# MCU-DESKTOP-L9L0IAD.net
KiCad netlist of a schematic drawn in Altium Designer
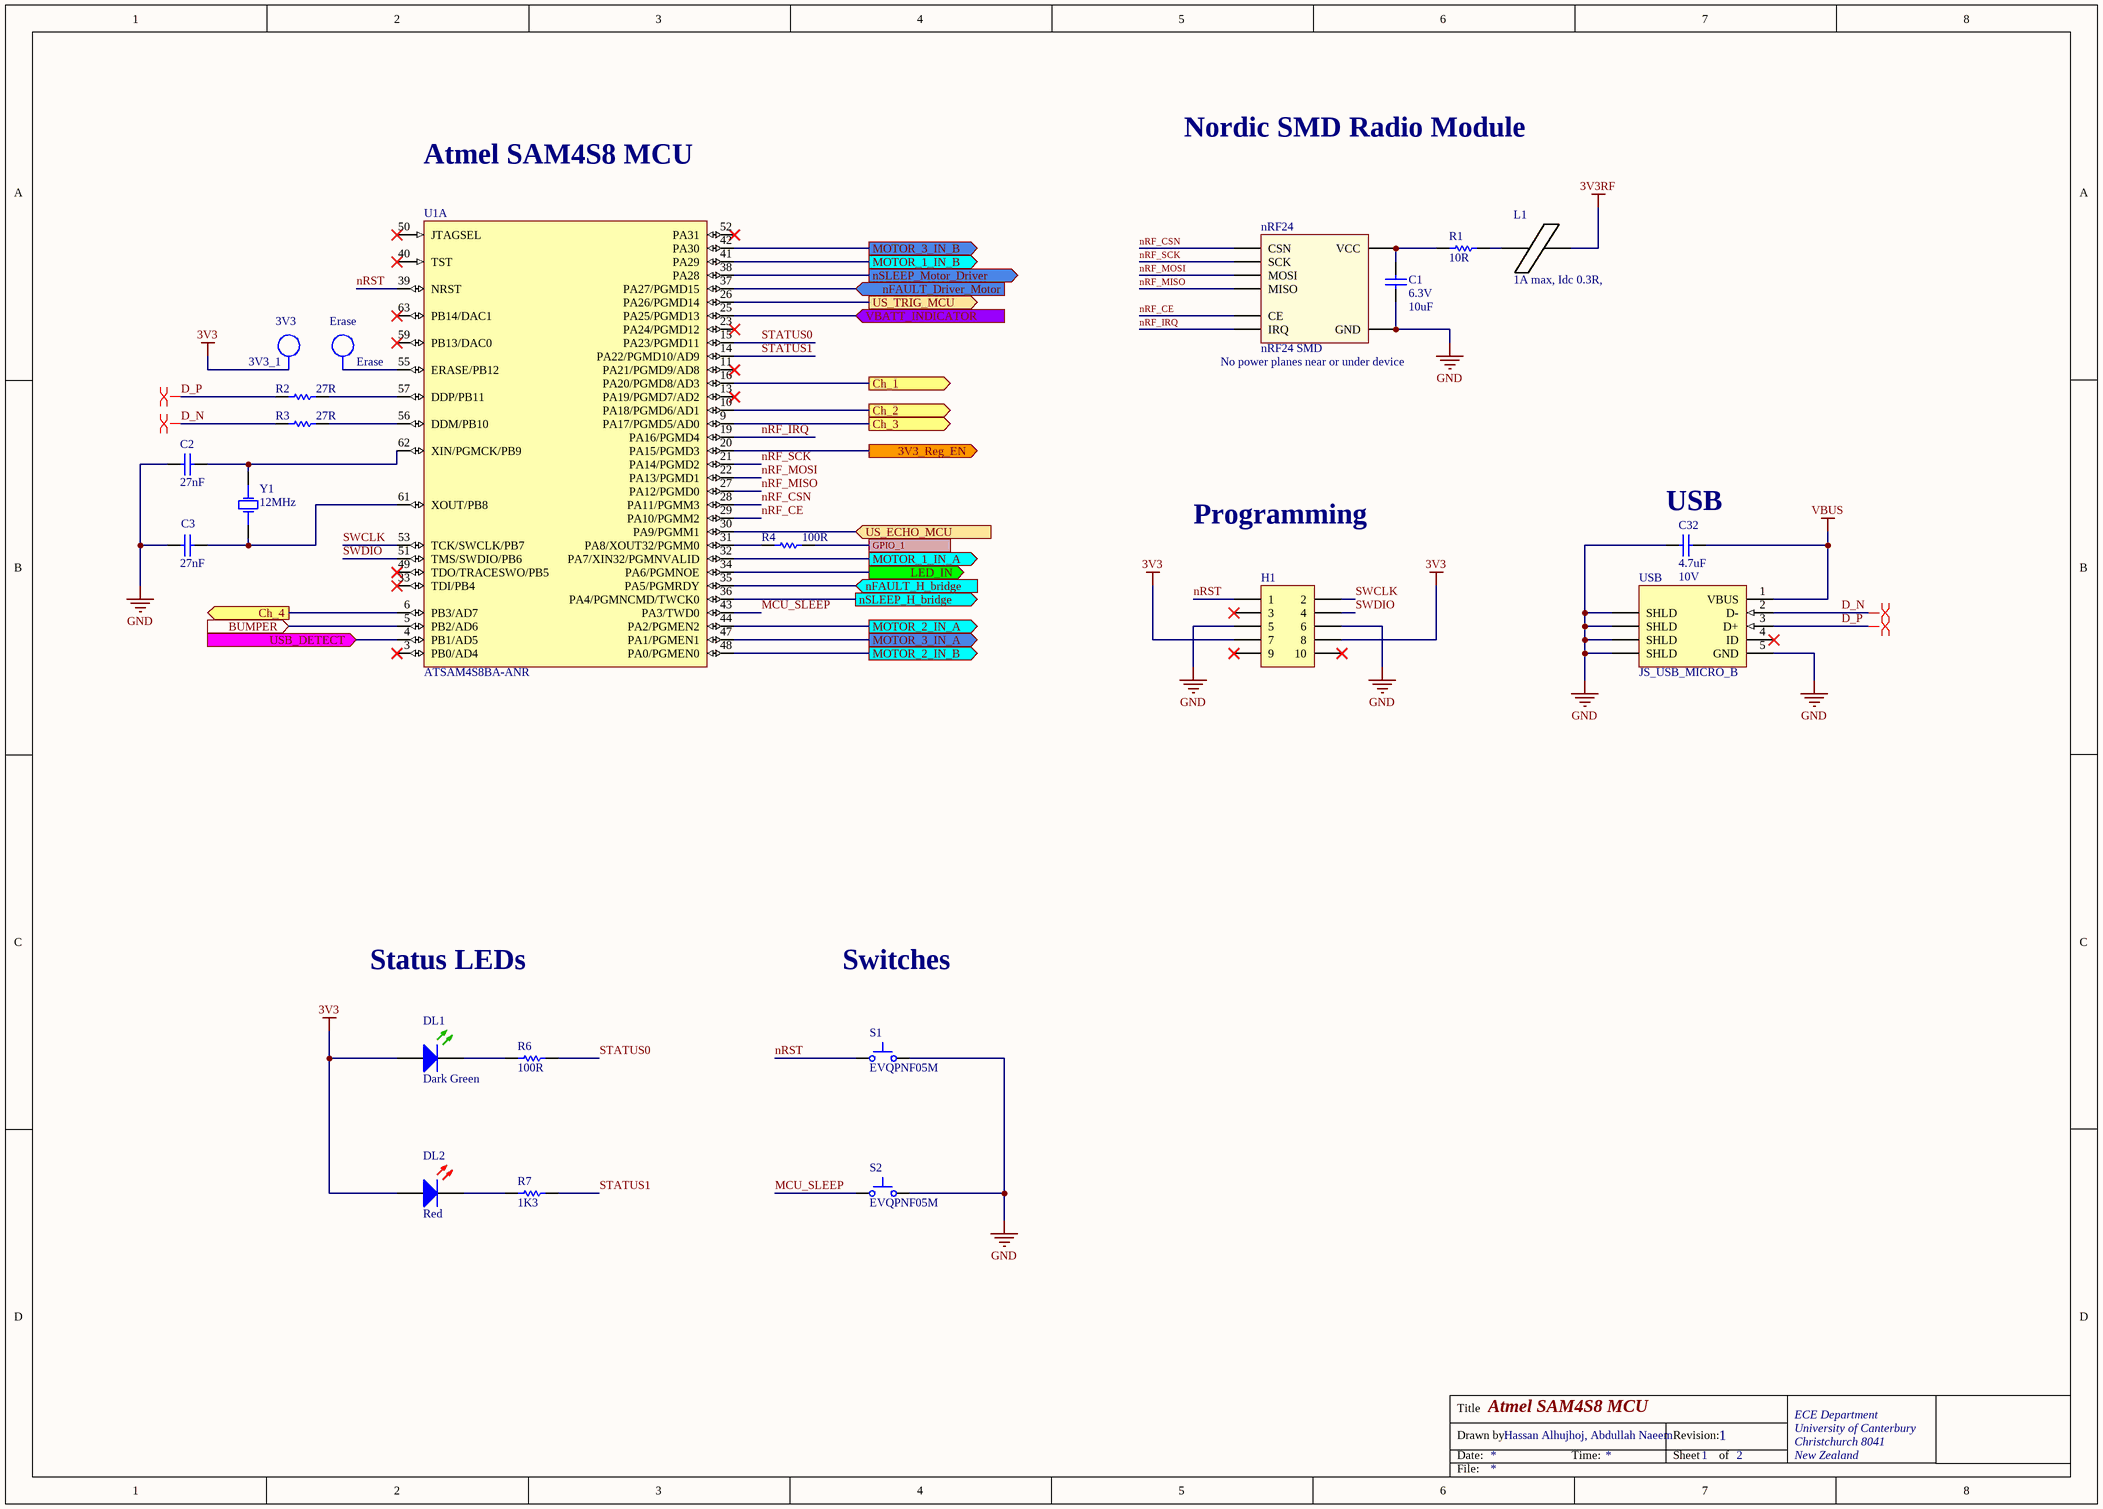
[diagram p0: MCU-DESKTOP-L9L0IAD.SchDoc]

(export (version "E")
  (design (tool "Eeschema 10.0.6"))
  (components
    (comp (ref "3V3_1")
      (value "TP")
      (footprint "TP_1206")
      (description "Test-Point 3.3x1.6x2.1mm SMD")
      (fields
        (field (name "MANUFACTURER") "Harwin Inc")
        (field (name "MANUFACTURER PART NUMBER") "S1751-46R")
      )
      (libsource (lib "ECE AD19Components_19V1") (part "TP_1206"))
    )
    (comp (ref "C1")
      (value "10uF")
      (footprint "CAPC1608L")
      (description "CAP CER 10UF X5R +-20% 6V3 0603")
      (fields (field (name "VOLTAGE - RATED") "6.3V"))
      (libsource (lib "ECE AD19Components_19V1") (part "CC_10uF_0603"))
    )
    (comp (ref "C2")
      (value "27nF")
      (footprint "CAPC1608L")
      (description "CAP CER 27nF X7R +-10% 50V 0603")
      (libsource (lib "ECE AD19Components_19V1") (part "CC_27nF_0603"))
    )
    (comp (ref "C3")
      (value "27nF")
      (footprint "CAPC1608L")
      (description "CAP CER 27nF X7R +-10% 50V 0603")
      (libsource (lib "ECE AD19Components_19V1") (part "CC_27nF_0603"))
    )
    (comp (ref "C32")
      (value "4.7uF")
      (footprint "CAPC1608N")
      (description "CAP CER 4.7uF X5R +-20%  10V 0603")
      (fields (field (name "MAX VOLTAGE") "10V"))
      (libsource (lib "ECE AD19Components_19V1") (part "CC_4.7uF_0603"))
    )
    (comp (ref "DL1")
      (value "Dark Green")
      (footprint "WL-SMCW0603")
      (description "LED Dk Green 430mcd 0603 SMD")
      (fields
        (field (name "MANUFACTURER") "WURTH ELEKTRONIK")
        (field (name "MANUFACTURER PART NUMBER") "150060GS75000")
        (field (name "LED COLOUR") "Dark Green")
      )
      (libsource (lib "ECE AD19Components_19V1") (part "DL_150060GS75000"))
    )
    (comp (ref "DL2")
      (value "Red")
      (footprint "WL-SMCW0603")
      (description "LED Red 250mcd 0603 SMD")
      (fields
        (field (name "MANUFACTURER") "WURTH ELEKTRONIK")
        (field (name "MANUFACTURER PART NUMBER") "150060RS75000")
        (field (name "LED COLOUR") "Red")
      )
      (libsource (lib "ECE AD19Components_19V1") (part "DL_150060RS75000"))
    )
    (comp (ref "Erase")
      (value "TP")
      (footprint "TP_1206")
      (description "Test-Point 3.3x1.6x2.1mm SMD")
      (fields
        (field (name "MANUFACTURER") "Harwin Inc")
        (field (name "MANUFACTURER PART NUMBER") "S1751-46R")
      )
      (libsource (lib "ECE AD19Components_19V1") (part "TP_1206"))
    )
    (comp (ref "H1")
      (value "Header 5X2 Vert")
      (footprint "IDC2.54-V10D")
      (description "IDC Header, 2,54mm, 10-Pin, Vert")
      (libsource (lib "ECE AD19Components_19V1") (part "JA_HDR_IDC_5X2_VERT"))
    )
    (comp (ref "L1")
      (value "1A max, Idc 0.3R,")
      (footprint "INDC3216L")
      (description "Ferrite Bead, Rdc 0.3R, Z100MHZ 600R, Imax 1A, SMD 1206")
      (fields
        (field (name "MANUFACTURER") "FAIR-RITE")
        (field (name "MANUFACTURER PART NUMBER") "2512066017Y1")
      )
      (libsource (lib "ECE AD19Components_19V1") (part "IN_Ferrite-Bead"))
    )
    (comp (ref "nRF24")
      (value "nRF24 SMD")
      (footprint "NRF24")
      (description "nRF24 SMD Module")
      (fields (field (name "WARNING") "No power planes near or under device"))
      (libsource (lib "ENCE461AD19_19V2") (part "NRF24"))
    )
    (comp (ref "R1")
      (value "10R")
      (footprint "RESC1608L")
      (description "RES 10 OHM 1/10W 5% 0603 SMD")
      (libsource (lib "ECE AD19Components_19V1") (part "RS_10R"))
    )
    (comp (ref "R2")
      (value "27R")
      (footprint "RESC1608L")
      (description "RES 27 OHM 1/10W 5% 0603 SMD")
      (libsource (lib "ECE AD19Components_19V1") (part "RS_27R"))
    )
    (comp (ref "R3")
      (value "27R")
      (footprint "RESC1608L")
      (description "RES 27 OHM 1/10W 5% 0603 SMD")
      (libsource (lib "ECE AD19Components_19V1") (part "RS_27R"))
    )
    (comp (ref "R4")
      (value "100R")
      (footprint "RESC1608L")
      (description "RES 100 OHM 1/10W 5% 0603 SMD")
      (libsource (lib "ECE AD19Components_19V1") (part "RS_100R"))
    )
    (comp (ref "R6")
      (value "100R")
      (footprint "RESC1608L")
      (description "RES 100 OHM 1/10W 5% 0603 SMD")
      (libsource (lib "ECE AD19Components_19V1") (part "RS_100R"))
    )
    (comp (ref "R7")
      (value "1K3")
      (footprint "RESC1608L")
      (description "RES 1.3K OHM 1/10W 5% 0603 SMD")
      (libsource (lib "ECE AD19Components_19V1") (part "RS_1K3"))
    )
    (comp (ref "S1")
      (value "EVQPNF05M")
      (footprint "EVQPNF05M")
      (description "Panasonic 6 x 3.5mm SMD Light Touch Switch Type SMD")
      (fields (field (name "MANUFACTURER") "Panasonic"))
      (libsource (lib "ECE AD19Components_19V1") (part "WS_EVQPNF05M"))
    )
    (comp (ref "S2")
      (value "EVQPNF05M")
      (footprint "EVQPNF05M")
      (description "Panasonic 6 x 3.5mm SMD Light Touch Switch Type SMD")
      (fields (field (name "MANUFACTURER") "Panasonic"))
      (libsource (lib "ECE AD19Components_19V1") (part "WS_EVQPNF05M"))
    )
    (comp (ref "U1")
      (value "ATSAM4S8BA-ANR")
      (footprint "LQFP64_L")
      (description "IC MCU 32BIT 512KB FLASH 64LQFP")
      (fields (field (name "MANUFACTURER") "Atmel"))
      (libsource (lib "ECE AD19Components_19V1") (part "SE_ATSAM4S16BA-MU"))
    )
    (comp (ref "USB")
      (value "JS_USB_MICRO_B")
      (footprint "FCI_USB_10118194-0001LF")
      (description "CONN USB MICRO B RECPT SMT R/A")
      (fields (field (name "MANUFACTURER") "FCI") (field (name "MANUFACTURER PART NUMBER") "10118194-0001LF"))
      (libsource (lib "ECE AD19Components_19V1") (part "JS_USB_MICRO_B_SMT"))
    )
    (comp (ref "Y1")
      (value "12MHz")
      (footprint "6.0X3.5-4")
      (description "CRYSTAL 12MHZ 18PF 6X3.5mm SMD")
      (fields
        (field (name "MANUFACTURER") "CTS-Frequency Controls")
        (field (name "MANUFACTURER PART NUMBER") "406C35D12M00000")
        (field (name "FREQUENCY") "12MHz")
      )
      (libsource (lib "ECE AD19Components_19V1") (part "XT_CRYSTAL_12MHz_18pF"))
    )
  )
  (nets
    (net (code "1") (name "/3V3_Reg_EN") (class "Default")
      (node (ref "U1") (pin "20") (pinfunction "PA15/PGMD3_20") (pintype "bidirectional"))
    )
    (net (code "2") (name "/BUMPER") (class "Default")
      (node (ref "U1") (pin "5") (pinfunction "PB2/AD6_5") (pintype "bidirectional"))
    )
    (net (code "3") (name "/Ch_1") (class "Default")
      (node (ref "U1") (pin "16") (pinfunction "PA20/PGMD8/AD3_16") (pintype "bidirectional"))
    )
    (net (code "4") (name "/Ch_2") (class "Default")
      (node (ref "U1") (pin "10") (pinfunction "PA18/PGMD6/AD1_10") (pintype "bidirectional"))
    )
    (net (code "5") (name "/Ch_3") (class "Default")
      (node (ref "U1") (pin "9") (pinfunction "PA17/PGMD5/AD0_9") (pintype "bidirectional"))
    )
    (net (code "6") (name "/Ch_4") (class "Default")
      (node (ref "U1") (pin "6") (pinfunction "PB3/AD7_6") (pintype "bidirectional"))
    )
    (net (code "7") (name "/D_N") (class "Default")
      (node (ref "R3") (pin "1") (pinfunction "1_1") (pintype "passive"))
      (node (ref "USB") (pin "2") (pinfunction "D-_2") (pintype "input"))
    )
    (net (code "8") (name "/D_P") (class "Default")
      (node (ref "R2") (pin "1") (pinfunction "1_1") (pintype "passive"))
      (node (ref "USB") (pin "3") (pinfunction "D+_3") (pintype "input"))
    )
    (net (code "9") (name "/GPIO_1") (class "Default")
      (node (ref "R4") (pin "2") (pinfunction "2_2") (pintype "passive"))
    )
    (net (code "10") (name "/LED_IN") (class "Default")
      (node (ref "U1") (pin "34") (pinfunction "PA6/PGMNOE_34") (pintype "bidirectional"))
    )
    (net (code "11") (name "/MCU_SLEEP") (class "Default")
      (node (ref "S2") (pin "1") (pintype "passive"))
      (node (ref "U1") (pin "43") (pinfunction "PA3/TWD0_43") (pintype "bidirectional"))
    )
    (net (code "12") (name "/MOTOR_1_IN_A") (class "Default")
      (node (ref "U1") (pin "32") (pinfunction "PA7/XIN32/PGMNVALID_32") (pintype "bidirectional"))
    )
    (net (code "13") (name "/MOTOR_1_IN_B") (class "Default")
      (node (ref "U1") (pin "41") (pinfunction "PA29_41") (pintype "bidirectional"))
    )
    (net (code "14") (name "/MOTOR_2_IN_A") (class "Default")
      (node (ref "U1") (pin "44") (pinfunction "PA2/PGMEN2_44") (pintype "bidirectional"))
    )
    (net (code "15") (name "/MOTOR_2_IN_B") (class "Default")
      (node (ref "U1") (pin "48") (pinfunction "PA0/PGMEN0_48") (pintype "bidirectional"))
    )
    (net (code "16") (name "/MOTOR_3_IN_A") (class "Default")
      (node (ref "U1") (pin "47") (pinfunction "PA1/PGMEN1_47") (pintype "bidirectional"))
    )
    (net (code "17") (name "/MOTOR_3_IN_B") (class "Default")
      (node (ref "U1") (pin "42") (pinfunction "PA30_42") (pintype "bidirectional"))
    )
    (net (code "18") (name "/STATUS0") (class "Default")
      (node (ref "R6") (pin "2") (pinfunction "2_2") (pintype "passive"))
      (node (ref "U1") (pin "15") (pinfunction "PA23/PGMD11_15") (pintype "bidirectional"))
    )
    (net (code "19") (name "/STATUS1") (class "Default")
      (node (ref "R7") (pin "2") (pinfunction "2_2") (pintype "passive"))
      (node (ref "U1") (pin "14") (pinfunction "PA22/PGMD10/AD9_14") (pintype "bidirectional"))
    )
    (net (code "20") (name "/SWCLK") (class "Default")
      (node (ref "H1") (pin "2") (pinfunction "2_2") (pintype "passive"))
      (node (ref "U1") (pin "53") (pinfunction "TCK/SWCLK/PB7_53") (pintype "bidirectional"))
    )
    (net (code "21") (name "/SWDIO") (class "Default")
      (node (ref "H1") (pin "4") (pinfunction "4_4") (pintype "passive"))
      (node (ref "U1") (pin "51") (pinfunction "TMS/SWDIO/PB6_51") (pintype "bidirectional"))
    )
    (net (code "22") (name "/USB_DETECT") (class "Default")
      (node (ref "U1") (pin "4") (pinfunction "PB1/AD5_4") (pintype "bidirectional"))
    )
    (net (code "23") (name "/US_ECHO_MCU") (class "Default")
      (node (ref "U1") (pin "30") (pinfunction "PA9/PGMM1_30") (pintype "bidirectional"))
    )
    (net (code "24") (name "/US_TRIG_MCU") (class "Default")
      (node (ref "U1") (pin "26") (pinfunction "PA26/PGMD14_26") (pintype "bidirectional"))
    )
    (net (code "25") (name "/VBATT_INDICATOR") (class "Default")
      (node (ref "U1") (pin "25") (pinfunction "PA25/PGMD13_25") (pintype "bidirectional"))
    )
    (net (code "26") (name "/nFAULT_Driver_Motor") (class "Default")
      (node (ref "U1") (pin "37") (pinfunction "PA27/PGMD15_37") (pintype "bidirectional"))
    )
    (net (code "27") (name "/nFAULT_H_bridge") (class "Default")
      (node (ref "U1") (pin "35") (pinfunction "PA5/PGMRDY_35") (pintype "bidirectional"))
    )
    (net (code "28") (name "/nRF_CE") (class "Default")
      (node (ref "U1") (pin "29") (pinfunction "PA10/PGMM2_29") (pintype "bidirectional"))
      (node (ref "nRF24") (pin "3") (pinfunction "CE_3") (pintype "passive"))
    )
    (net (code "29") (name "/nRF_CSN") (class "Default")
      (node (ref "U1") (pin "28") (pinfunction "PA11/PGMM3_28") (pintype "bidirectional"))
      (node (ref "nRF24") (pin "4") (pinfunction "CSN_4") (pintype "passive"))
    )
    (net (code "30") (name "/nRF_IRQ") (class "Default")
      (node (ref "U1") (pin "19") (pinfunction "PA16/PGMD4_19") (pintype "bidirectional"))
      (node (ref "nRF24") (pin "8") (pinfunction "IRQ_8") (pintype "passive"))
    )
    (net (code "31") (name "/nRF_MISO") (class "Default")
      (node (ref "U1") (pin "27") (pinfunction "PA12/PGMD0_27") (pintype "bidirectional"))
      (node (ref "nRF24") (pin "7") (pinfunction "MISO_7") (pintype "passive"))
    )
    (net (code "32") (name "/nRF_MOSI") (class "Default")
      (node (ref "U1") (pin "22") (pinfunction "PA13/PGMD1_22") (pintype "bidirectional"))
      (node (ref "nRF24") (pin "6") (pinfunction "MOSI_6") (pintype "passive"))
    )
    (net (code "33") (name "/nRF_SCK") (class "Default")
      (node (ref "U1") (pin "21") (pinfunction "PA14/PGMD2_21") (pintype "bidirectional"))
      (node (ref "nRF24") (pin "5") (pinfunction "SCK_5") (pintype "passive"))
    )
    (net (code "34") (name "/nRST") (class "Default")
      (node (ref "H1") (pin "1") (pinfunction "1_1") (pintype "passive"))
      (node (ref "S1") (pin "1") (pintype "passive"))
      (node (ref "U1") (pin "39") (pinfunction "NRST_39") (pintype "bidirectional"))
    )
    (net (code "35") (name "/nSLEEP_H_bridge") (class "Default")
      (node (ref "U1") (pin "36") (pinfunction "PA4/PGMNCMD/TWCK0_36") (pintype "bidirectional"))
    )
    (net (code "36") (name "/nSLEEP_Motor_Driver") (class "Default")
      (node (ref "U1") (pin "38") (pinfunction "PA28_38") (pintype "bidirectional"))
    )
    (net (code "37") (name "3V3") (class "Default")
      (node (ref "3V3_1") (pin "1") (pinfunction "1_1") (pintype "passive"))
      (node (ref "DL1") (pin "2") (pinfunction "A_2") (pintype "passive"))
      (node (ref "DL2") (pin "2") (pinfunction "A_2") (pintype "passive"))
      (node (ref "H1") (pin "7") (pinfunction "7_7") (pintype "passive"))
      (node (ref "H1") (pin "8") (pinfunction "8_8") (pintype "passive"))
    )
    (net (code "38") (name "3V3RF") (class "Default")
      (node (ref "L1") (pin "2") (pinfunction "2_2") (pintype "passive"))
    )
    (net (code "39") (name "GND") (class "Default")
      (node (ref "C1") (pin "1") (pinfunction "1_1") (pintype "passive"))
      (node (ref "C2") (pin "1") (pinfunction "1_1") (pintype "passive"))
      (node (ref "C3") (pin "1") (pinfunction "1_1") (pintype "passive"))
      (node (ref "C32") (pin "1") (pinfunction "1_1") (pintype "passive"))
      (node (ref "H1") (pin "5") (pinfunction "5_5") (pintype "passive"))
      (node (ref "H1") (pin "6") (pinfunction "6_6") (pintype "passive"))
      (node (ref "S1") (pin "2") (pintype "passive"))
      (node (ref "S2") (pin "2") (pintype "passive"))
      (node (ref "USB") (pin "5") (pinfunction "GND_5") (pintype "passive"))
      (node (ref "USB") (pin "6") (pinfunction "SHLD_6") (pintype "passive"))
      (node (ref "nRF24") (pin "2") (pinfunction "GND_2") (pintype "passive"))
    )
    (net (code "40") (name "Net-(DL1-K)") (class "Default")
      (node (ref "DL1") (pin "1") (pinfunction "K_1") (pintype "passive"))
      (node (ref "R6") (pin "1") (pinfunction "1_1") (pintype "passive"))
    )
    (net (code "41") (name "Net-(DL2-K)") (class "Default")
      (node (ref "DL2") (pin "1") (pinfunction "K_1") (pintype "passive"))
      (node (ref "R7") (pin "1") (pinfunction "1_1") (pintype "passive"))
    )
    (net (code "42") (name "Net-(L1-Pad1)") (class "Default")
      (node (ref "L1") (pin "1") (pinfunction "1_1") (pintype "passive"))
      (node (ref "R1") (pin "2") (pinfunction "2_2") (pintype "passive"))
    )
    (net (code "43") (name "Net-(U1A-DDM{slash}PB10)") (class "Default")
      (node (ref "R3") (pin "2") (pinfunction "2_2") (pintype "passive"))
      (node (ref "U1") (pin "56") (pinfunction "DDM/PB10_56") (pintype "bidirectional"))
    )
    (net (code "44") (name "Net-(U1A-DDP{slash}PB11)") (class "Default")
      (node (ref "R2") (pin "2") (pinfunction "2_2") (pintype "passive"))
      (node (ref "U1") (pin "57") (pinfunction "DDP/PB11_57") (pintype "bidirectional"))
    )
    (net (code "45") (name "Net-(U1A-ERASE{slash}PB12)") (class "Default")
      (node (ref "Erase") (pin "1") (pinfunction "1_1") (pintype "passive"))
      (node (ref "U1") (pin "55") (pinfunction "ERASE/PB12_55") (pintype "bidirectional"))
    )
    (net (code "46") (name "Net-(U1A-PA8{slash}XOUT32{slash}PGMM0)") (class "Default")
      (node (ref "R4") (pin "1") (pinfunction "1_1") (pintype "passive"))
      (node (ref "U1") (pin "31") (pinfunction "PA8/XOUT32/PGMM0_31") (pintype "bidirectional"))
    )
    (net (code "47") (name "Net-(U1A-XIN{slash}PGMCK{slash}PB9)") (class "Default")
      (node (ref "C2") (pin "2") (pinfunction "2_2") (pintype "passive"))
      (node (ref "U1") (pin "62") (pinfunction "XIN/PGMCK/PB9_62") (pintype "bidirectional"))
      (node (ref "Y1") (pin "3") (pinfunction "OSC2_3") (pintype "passive"))
    )
    (net (code "48") (name "Net-(U1A-XOUT{slash}PB8)") (class "Default")
      (node (ref "C3") (pin "2") (pinfunction "2_2") (pintype "passive"))
      (node (ref "U1") (pin "61") (pinfunction "XOUT/PB8_61") (pintype "bidirectional"))
      (node (ref "Y1") (pin "1") (pinfunction "OSC1_1") (pintype "passive"))
    )
    (net (code "49") (name "Net-(nRF24-VCC)") (class "Default")
      (node (ref "C1") (pin "2") (pinfunction "2_2") (pintype "passive"))
      (node (ref "R1") (pin "1") (pinfunction "1_1") (pintype "passive"))
      (node (ref "nRF24") (pin "1") (pinfunction "VCC_1") (pintype "passive"))
    )
    (net (code "50") (name "VBUS") (class "Default")
      (node (ref "C32") (pin "2") (pinfunction "2_2") (pintype "passive"))
      (node (ref "USB") (pin "1") (pinfunction "VBUS_1") (pintype "power_in"))
    )
    (net (code "51") (name "unconnected-(H1-Pad3)") (class "Default")
      (node (ref "H1") (pin "3") (pinfunction "3_3") (pintype "passive+no_connect"))
    )
    (net (code "52") (name "unconnected-(H1-Pad9)") (class "Default")
      (node (ref "H1") (pin "9") (pinfunction "9_9") (pintype "passive+no_connect"))
    )
    (net (code "53") (name "unconnected-(H1-Pad10)") (class "Default")
      (node (ref "H1") (pin "10") (pinfunction "10_10") (pintype "passive+no_connect"))
    )
    (net (code "54") (name "unconnected-(U1A-JTAGSEL-Pad50)") (class "Default")
      (node (ref "U1") (pin "50") (pinfunction "JTAGSEL_50") (pintype "input+no_connect"))
    )
    (net (code "55") (name "unconnected-(U1A-PA19{slash}PGMD7{slash}AD2-Pad13)") (class "Default")
      (node (ref "U1") (pin "13") (pinfunction "PA19/PGMD7/AD2_13") (pintype "bidirectional+no_connect"))
    )
    (net (code "56") (name "unconnected-(U1A-PA21{slash}PGMD9{slash}AD8-Pad11)") (class "Default")
      (node (ref "U1") (pin "11") (pinfunction "PA21/PGMD9/AD8_11") (pintype "bidirectional+no_connect"))
    )
    (net (code "57") (name "unconnected-(U1A-PA24{slash}PGMD12-Pad23)") (class "Default")
      (node (ref "U1") (pin "23") (pinfunction "PA24/PGMD12_23") (pintype "bidirectional+no_connect"))
    )
    (net (code "58") (name "unconnected-(U1A-PA31-Pad52)") (class "Default")
      (node (ref "U1") (pin "52") (pinfunction "PA31_52") (pintype "bidirectional+no_connect"))
    )
    (net (code "59") (name "unconnected-(U1A-PB0{slash}AD4-Pad3)") (class "Default")
      (node (ref "U1") (pin "3") (pinfunction "PB0/AD4_3") (pintype "bidirectional+no_connect"))
    )
    (net (code "60") (name "unconnected-(U1A-PB13{slash}DAC0-Pad59)") (class "Default")
      (node (ref "U1") (pin "59") (pinfunction "PB13/DAC0_59") (pintype "bidirectional+no_connect"))
    )
    (net (code "61") (name "unconnected-(U1A-PB14{slash}DAC1-Pad63)") (class "Default")
      (node (ref "U1") (pin "63") (pinfunction "PB14/DAC1_63") (pintype "bidirectional+no_connect"))
    )
    (net (code "62") (name "unconnected-(U1A-TDI{slash}PB4-Pad33)") (class "Default")
      (node (ref "U1") (pin "33") (pinfunction "TDI/PB4_33") (pintype "bidirectional+no_connect"))
    )
    (net (code "63") (name "unconnected-(U1A-TDO{slash}TRACESWO{slash}PB5-Pad49)") (class "Default")
      (node (ref "U1") (pin "49") (pinfunction "TDO/TRACESWO/PB5_49") (pintype "bidirectional+no_connect"))
    )
    (net (code "64") (name "unconnected-(U1A-TST-Pad40)") (class "Default")
      (node (ref "U1") (pin "40") (pinfunction "TST_40") (pintype "input+no_connect"))
    )
    (net (code "65") (name "unconnected-(USB-ID-Pad4)") (class "Default")
      (node (ref "USB") (pin "4") (pinfunction "ID_4") (pintype "power_in+no_connect"))
    )
  )
)
